# VoltageRegulator.net
KiCad netlist of a schematic drawn in EAGLE
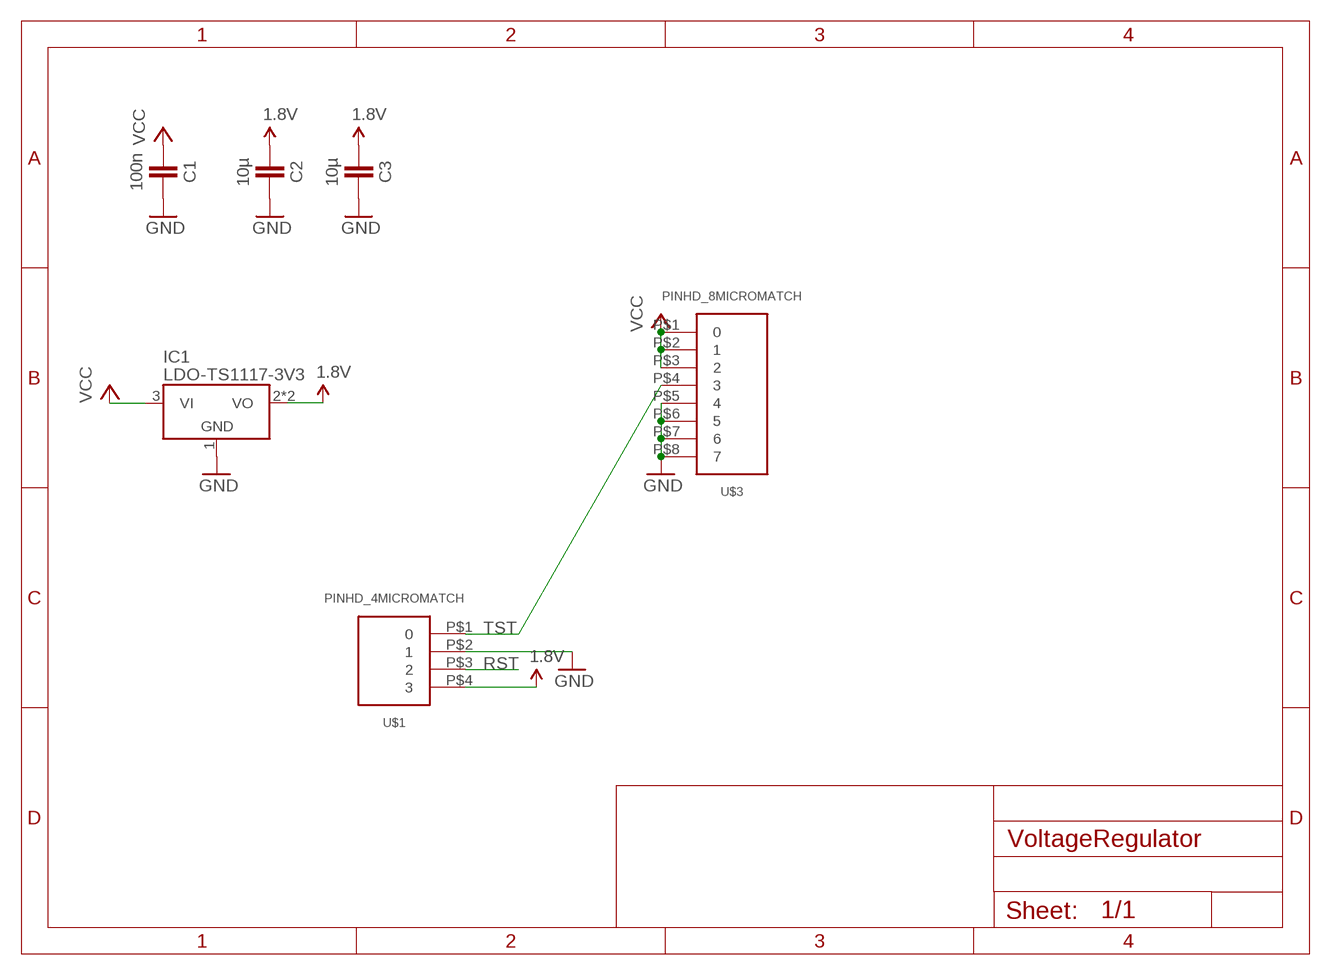
[diagram p0: schematic, sheet 1]

(export (version "E")
  (design (tool "Eeschema 10.0.6"))
  (components
    (comp (ref "C1")
      (value "100n")
      (footprint "eagle-import:1206")
      (libsource (lib "eagle-import") (part "CAPACITOR1206"))
    )
    (comp (ref "C2")
      (value "10µ")
      (footprint "eagle-import:1206")
      (libsource (lib "eagle-import") (part "CAPACITOR1206"))
    )
    (comp (ref "C3")
      (value "10µ")
      (footprint "eagle-import:1206")
      (libsource (lib "eagle-import") (part "CAPACITOR1206"))
    )
    (comp (ref "IC1")
      (value "LDO-TS1117-3V3")
      (footprint "eagle-import:SOT223")
      (libsource (lib "eagle-import") (part "LDO-TS1117-3V3"))
    )
    (comp (ref "U$1")
      (value "PINHD_4MICROMATCH")
      (footprint "eagle-import:MICROMATCH4P0L")
      (libsource (lib "eagle-import") (part "PINHD_4MICROMATCH"))
    )
    (comp (ref "U$3")
      (value "PINHD_8MICROMATCH")
      (footprint "eagle-import:MICROMATCH8POL")
      (libsource (lib "eagle-import") (part "PINHD_8MICROMATCH"))
    )
  )
  (nets
    (net (code "1") (name "/RST") (class "Default")
      (node (ref "U$1") (pin "P$3") (pinfunction "2_P$3") (pintype "bidirectional"))
    )
    (net (code "2") (name "/TST") (class "Default")
      (node (ref "U$1") (pin "P$1") (pinfunction "0_P$1") (pintype "bidirectional"))
      (node (ref "U$3") (pin "P$4") (pinfunction "3_P$4") (pintype "bidirectional"))
    )
    (net (code "3") (name "1.8V") (class "Default")
      (node (ref "C2") (pin "1") (pinfunction "1_1") (pintype "passive"))
      (node (ref "C3") (pin "1") (pinfunction "1_1") (pintype "passive"))
      (node (ref "IC1") (pin "2") (pinfunction "VO_2") (pintype "passive"))
      (node (ref "IC1") (pin "4") (pinfunction "VO_4") (pintype "passive"))
      (node (ref "U$1") (pin "P$4") (pinfunction "3_P$4") (pintype "bidirectional"))
    )
    (net (code "4") (name "GND") (class "Default")
      (node (ref "C1") (pin "2") (pinfunction "2_2") (pintype "passive"))
      (node (ref "C2") (pin "2") (pinfunction "2_2") (pintype "passive"))
      (node (ref "C3") (pin "2") (pinfunction "2_2") (pintype "passive"))
      (node (ref "IC1") (pin "1") (pinfunction "GND_1") (pintype "passive"))
      (node (ref "U$1") (pin "P$2") (pinfunction "1_P$2") (pintype "bidirectional"))
      (node (ref "U$3") (pin "P$5") (pinfunction "4_P$5") (pintype "bidirectional"))
      (node (ref "U$3") (pin "P$6") (pinfunction "5_P$6") (pintype "bidirectional"))
      (node (ref "U$3") (pin "P$7") (pinfunction "6_P$7") (pintype "bidirectional"))
      (node (ref "U$3") (pin "P$8") (pinfunction "7_P$8") (pintype "bidirectional"))
    )
    (net (code "5") (name "VCC") (class "Default")
      (node (ref "C1") (pin "1") (pinfunction "1_1") (pintype "passive"))
      (node (ref "IC1") (pin "3") (pinfunction "VI_3") (pintype "input"))
      (node (ref "U$3") (pin "P$1") (pinfunction "0_P$1") (pintype "bidirectional"))
      (node (ref "U$3") (pin "P$2") (pinfunction "1_P$2") (pintype "bidirectional"))
      (node (ref "U$3") (pin "P$3") (pinfunction "2_P$3") (pintype "bidirectional"))
    )
  )
)
